# moduloComunicacao2.net
KiCad netlist of a schematic drawn in EAGLE
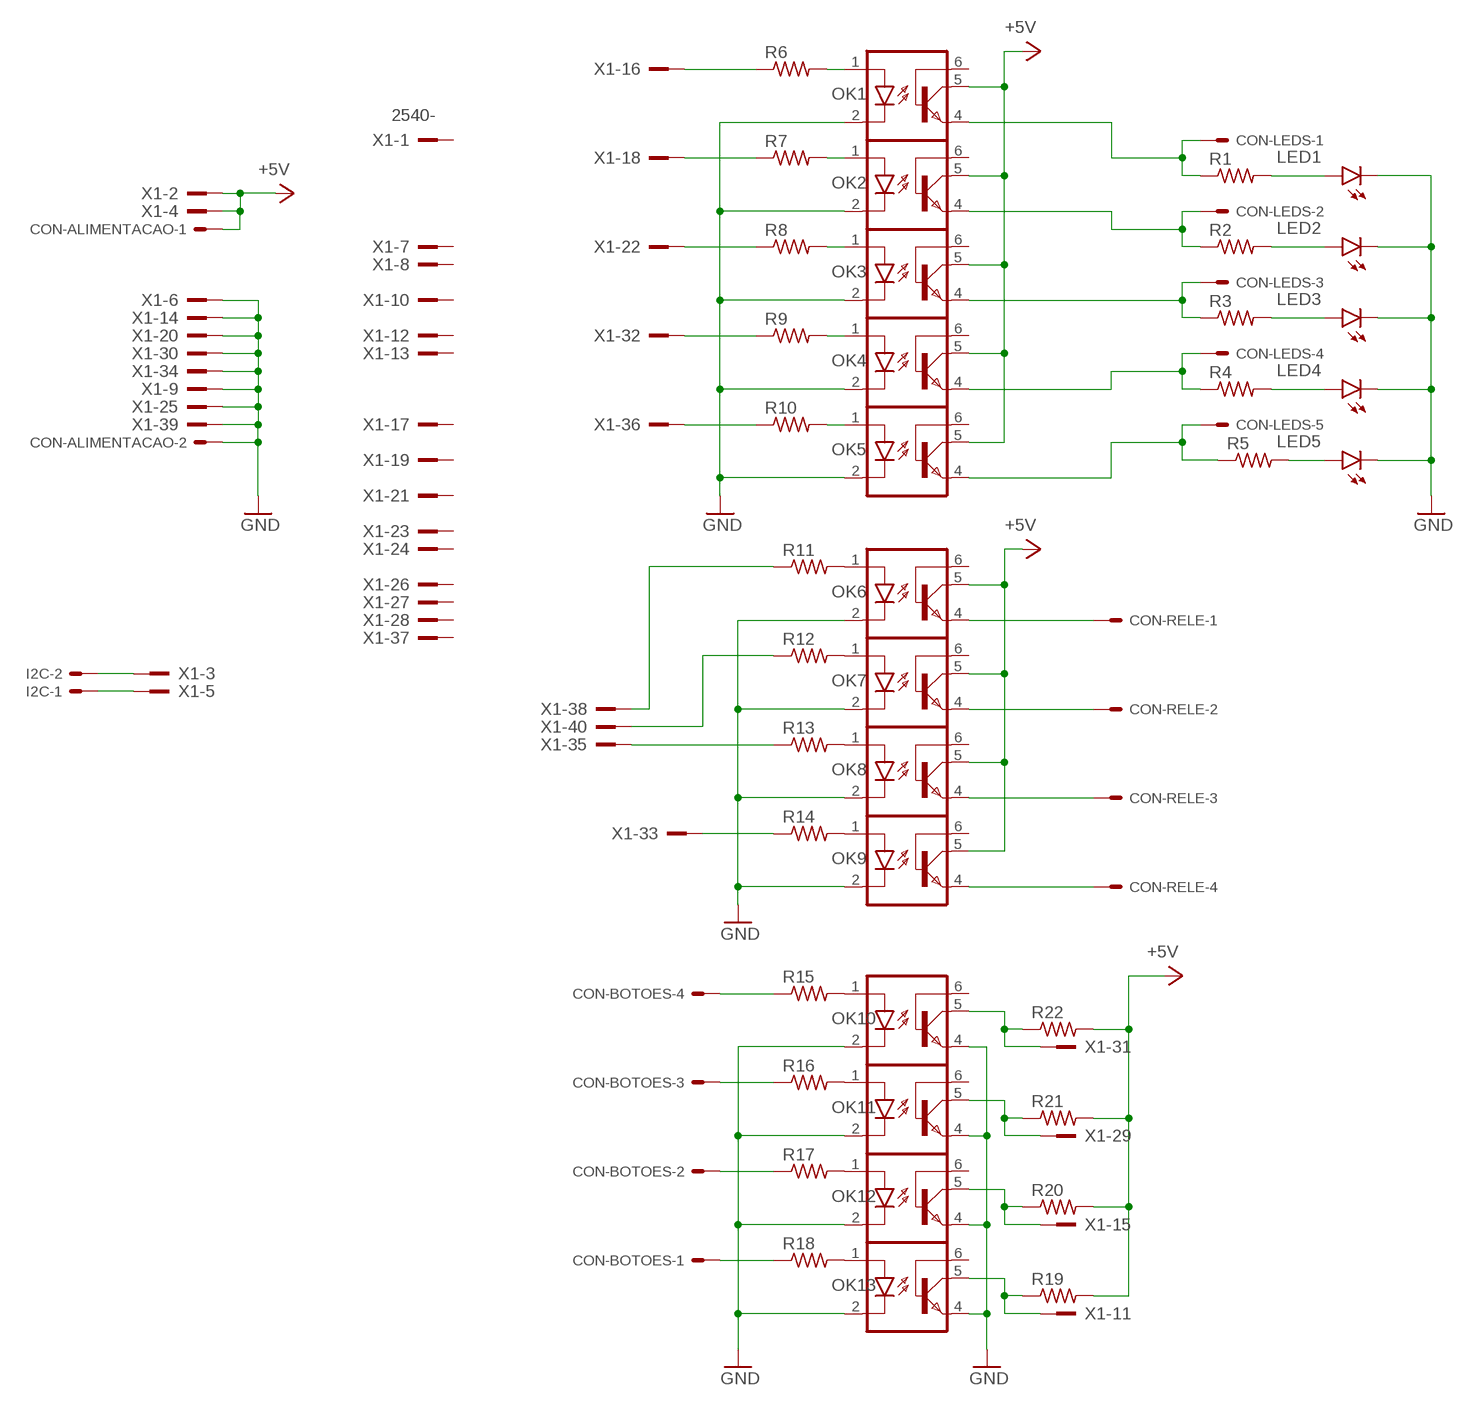
[diagram p0: schematic, sheet 1]

(export (version "E")
  (design (tool "Eeschema 10.0.6"))
  (components
    (comp (ref "CON-ALIMENTACAO")
      (value "22-23-2021")
      (footprint "eagle-import:22-23-2021")
      (fields (field (name "MF") "MOLEX"))
      (libsource (lib "eagle-import") (part "22-23-2021"))
    )
    (comp (ref "CON-BOTOES")
      (value "22-23-2041")
      (footprint "eagle-import:22-23-2041")
      (fields (field (name "MF") "MOLEX"))
      (libsource (lib "eagle-import") (part "22-23-2041"))
    )
    (comp (ref "CON-LEDS")
      (value "22-23-2051")
      (footprint "eagle-import:22-23-2051")
      (fields (field (name "MF") "MOLEX"))
      (libsource (lib "eagle-import") (part "22-23-2051"))
    )
    (comp (ref "CON-RELE")
      (value "22-23-2041")
      (footprint "eagle-import:22-23-2041")
      (fields (field (name "MF") "MOLEX"))
      (libsource (lib "eagle-import") (part "22-23-2041"))
    )
    (comp (ref "I2C")
      (value "22-23-2021")
      (footprint "eagle-import:22-23-2021")
      (fields (field (name "MF") "MOLEX"))
      (libsource (lib "eagle-import") (part "22-23-2021"))
    )
    (comp (ref "LED1")
      (value "LED5MM")
      (footprint "eagle-import:LED5MM")
      (libsource (lib "eagle-import") (part "LED5MM"))
    )
    (comp (ref "LED2")
      (value "LED5MM")
      (footprint "eagle-import:LED5MM")
      (libsource (lib "eagle-import") (part "LED5MM"))
    )
    (comp (ref "LED3")
      (value "LED5MM")
      (footprint "eagle-import:LED5MM")
      (libsource (lib "eagle-import") (part "LED5MM"))
    )
    (comp (ref "LED4")
      (value "LED5MM")
      (footprint "eagle-import:LED5MM")
      (libsource (lib "eagle-import") (part "LED5MM"))
    )
    (comp (ref "LED5")
      (value "LED5MM")
      (footprint "eagle-import:LED5MM")
      (libsource (lib "eagle-import") (part "LED5MM"))
    )
    (comp (ref "OK1")
      (value "4N25M")
      (footprint "eagle-import:DIL06")
      (fields (field (name "MPN") "4N25-M"))
      (libsource (lib "eagle-import") (part "4N?M25"))
    )
    (comp (ref "OK2")
      (value "4N25M")
      (footprint "eagle-import:DIL06")
      (fields (field (name "MPN") "4N25-M"))
      (libsource (lib "eagle-import") (part "4N?M25"))
    )
    (comp (ref "OK3")
      (value "4N25M")
      (footprint "eagle-import:DIL06")
      (fields (field (name "MPN") "4N25-M"))
      (libsource (lib "eagle-import") (part "4N?M25"))
    )
    (comp (ref "OK4")
      (value "4N25M")
      (footprint "eagle-import:DIL06")
      (fields (field (name "MPN") "4N25-M"))
      (libsource (lib "eagle-import") (part "4N?M25"))
    )
    (comp (ref "OK5")
      (value "4N25M")
      (footprint "eagle-import:DIL06")
      (fields (field (name "MPN") "4N25-M"))
      (libsource (lib "eagle-import") (part "4N?M25"))
    )
    (comp (ref "OK6")
      (value "4N25M")
      (footprint "eagle-import:DIL06")
      (fields (field (name "MPN") "4N25-M"))
      (libsource (lib "eagle-import") (part "4N?M25"))
    )
    (comp (ref "OK7")
      (value "4N25M")
      (footprint "eagle-import:DIL06")
      (fields (field (name "MPN") "4N25-M"))
      (libsource (lib "eagle-import") (part "4N?M25"))
    )
    (comp (ref "OK8")
      (value "4N25M")
      (footprint "eagle-import:DIL06")
      (fields (field (name "MPN") "4N25-M"))
      (libsource (lib "eagle-import") (part "4N?M25"))
    )
    (comp (ref "OK9")
      (value "4N25M")
      (footprint "eagle-import:DIL06")
      (fields (field (name "MPN") "4N25-M"))
      (libsource (lib "eagle-import") (part "4N?M25"))
    )
    (comp (ref "OK10")
      (value "4N25M")
      (footprint "eagle-import:DIL06")
      (fields (field (name "MPN") "4N25-M"))
      (libsource (lib "eagle-import") (part "4N?M25"))
    )
    (comp (ref "OK11")
      (value "4N25M")
      (footprint "eagle-import:DIL06")
      (fields (field (name "MPN") "4N25-M"))
      (libsource (lib "eagle-import") (part "4N?M25"))
    )
    (comp (ref "OK12")
      (value "4N25M")
      (footprint "eagle-import:DIL06")
      (fields (field (name "MPN") "4N25-M"))
      (libsource (lib "eagle-import") (part "4N?M25"))
    )
    (comp (ref "OK13")
      (value "4N25M")
      (footprint "eagle-import:DIL06")
      (fields (field (name "MPN") "4N25-M"))
      (libsource (lib "eagle-import") (part "4N?M25"))
    )
    (comp (ref "R1")
      (value "R-US_0207/12")
      (footprint "eagle-import:0207_12")
      (libsource (lib "eagle-import") (part "R-US_0207/12"))
    )
    (comp (ref "R2")
      (value "R-US_0207/12")
      (footprint "eagle-import:0207_12")
      (libsource (lib "eagle-import") (part "R-US_0207/12"))
    )
    (comp (ref "R3")
      (value "R-US_0207/12")
      (footprint "eagle-import:0207_12")
      (libsource (lib "eagle-import") (part "R-US_0207/12"))
    )
    (comp (ref "R4")
      (value "R-US_0207/12")
      (footprint "eagle-import:0207_12")
      (libsource (lib "eagle-import") (part "R-US_0207/12"))
    )
    (comp (ref "R5")
      (value "R-US_0207/12")
      (footprint "eagle-import:0207_12")
      (libsource (lib "eagle-import") (part "R-US_0207/12"))
    )
    (comp (ref "R6")
      (value "R-US_0204/7")
      (footprint "eagle-import:0204_7")
      (libsource (lib "eagle-import") (part "R-US_0204/7"))
    )
    (comp (ref "R7")
      (value "R-US_0204/7")
      (footprint "eagle-import:0204_7")
      (libsource (lib "eagle-import") (part "R-US_0204/7"))
    )
    (comp (ref "R8")
      (value "R-US_0204/7")
      (footprint "eagle-import:0204_7")
      (libsource (lib "eagle-import") (part "R-US_0204/7"))
    )
    (comp (ref "R9")
      (value "R-US_0204/7")
      (footprint "eagle-import:0204_7")
      (libsource (lib "eagle-import") (part "R-US_0204/7"))
    )
    (comp (ref "R10")
      (value "R-US_0204/7")
      (footprint "eagle-import:0204_7")
      (libsource (lib "eagle-import") (part "R-US_0204/7"))
    )
    (comp (ref "R11")
      (value "R-US_0204/7")
      (footprint "eagle-import:0204_7")
      (libsource (lib "eagle-import") (part "R-US_0204/7"))
    )
    (comp (ref "R12")
      (value "R-US_0204/7")
      (footprint "eagle-import:0204_7")
      (libsource (lib "eagle-import") (part "R-US_0204/7"))
    )
    (comp (ref "R13")
      (value "R-US_0204/7")
      (footprint "eagle-import:0204_7")
      (libsource (lib "eagle-import") (part "R-US_0204/7"))
    )
    (comp (ref "R14")
      (value "R-US_0204/7")
      (footprint "eagle-import:0204_7")
      (libsource (lib "eagle-import") (part "R-US_0204/7"))
    )
    (comp (ref "R15")
      (value "R-US_0207/10")
      (footprint "eagle-import:0207_10")
      (libsource (lib "eagle-import") (part "R-US_0207/10"))
    )
    (comp (ref "R16")
      (value "R-US_0207/10")
      (footprint "eagle-import:0207_10")
      (libsource (lib "eagle-import") (part "R-US_0207/10"))
    )
    (comp (ref "R17")
      (value "R-US_0207/10")
      (footprint "eagle-import:0207_10")
      (libsource (lib "eagle-import") (part "R-US_0207/10"))
    )
    (comp (ref "R18")
      (value "R-US_0207/10")
      (footprint "eagle-import:0207_10")
      (libsource (lib "eagle-import") (part "R-US_0207/10"))
    )
    (comp (ref "R19")
      (value "R-US_0204/7")
      (footprint "eagle-import:0204_7")
      (libsource (lib "eagle-import") (part "R-US_0204/7"))
    )
    (comp (ref "R20")
      (value "R-US_0204/7")
      (footprint "eagle-import:0204_7")
      (libsource (lib "eagle-import") (part "R-US_0204/7"))
    )
    (comp (ref "R21")
      (value "R-US_0204/7")
      (footprint "eagle-import:0204_7")
      (libsource (lib "eagle-import") (part "R-US_0204/7"))
    )
    (comp (ref "R22")
      (value "R-US_0204/7")
      (footprint "eagle-import:0204_7")
      (libsource (lib "eagle-import") (part "R-US_0204/7"))
    )
    (comp (ref "X1")
      (value "2540-")
      (footprint "eagle-import:PAK100_2500-40")
      (libsource (lib "eagle-import") (part "2540-"))
    )
  )
  (nets
    (net (code "1") (name "+5V") (class "Default")
      (node (ref "CON-ALIMENTACAO") (pin "1") (pinfunction "S_1") (pintype "passive"))
      (node (ref "OK1") (pin "5") (pinfunction "COL_5") (pintype "passive"))
      (node (ref "OK2") (pin "5") (pinfunction "COL_5") (pintype "passive"))
      (node (ref "OK3") (pin "5") (pinfunction "COL_5") (pintype "passive"))
      (node (ref "OK4") (pin "5") (pinfunction "COL_5") (pintype "passive"))
      (node (ref "OK5") (pin "5") (pinfunction "COL_5") (pintype "passive"))
      (node (ref "OK6") (pin "5") (pinfunction "COL_5") (pintype "passive"))
      (node (ref "OK7") (pin "5") (pinfunction "COL_5") (pintype "passive"))
      (node (ref "OK8") (pin "5") (pinfunction "COL_5") (pintype "passive"))
      (node (ref "OK9") (pin "5") (pinfunction "COL_5") (pintype "passive"))
      (node (ref "R19") (pin "2") (pinfunction "2_2") (pintype "passive"))
      (node (ref "R20") (pin "2") (pinfunction "2_2") (pintype "passive"))
      (node (ref "R21") (pin "2") (pinfunction "2_2") (pintype "passive"))
      (node (ref "R22") (pin "2") (pinfunction "2_2") (pintype "passive"))
      (node (ref "X1") (pin "2") (pinfunction "KL_2") (pintype "passive"))
      (node (ref "X1") (pin "4") (pinfunction "KL_4") (pintype "passive"))
    )
    (net (code "2") (name "GND") (class "Default")
      (node (ref "CON-ALIMENTACAO") (pin "2") (pinfunction "S_2") (pintype "passive"))
      (node (ref "LED1") (pin "K") (pinfunction "C_K") (pintype "passive"))
      (node (ref "LED2") (pin "K") (pinfunction "C_K") (pintype "passive"))
      (node (ref "LED3") (pin "K") (pinfunction "C_K") (pintype "passive"))
      (node (ref "LED4") (pin "K") (pinfunction "C_K") (pintype "passive"))
      (node (ref "LED5") (pin "K") (pinfunction "C_K") (pintype "passive"))
      (node (ref "OK1") (pin "2") (pinfunction "C_2") (pintype "passive"))
      (node (ref "OK10") (pin "2") (pinfunction "C_2") (pintype "passive"))
      (node (ref "OK10") (pin "4") (pinfunction "EMI_4") (pintype "passive"))
      (node (ref "OK11") (pin "2") (pinfunction "C_2") (pintype "passive"))
      (node (ref "OK11") (pin "4") (pinfunction "EMI_4") (pintype "passive"))
      (node (ref "OK12") (pin "2") (pinfunction "C_2") (pintype "passive"))
      (node (ref "OK12") (pin "4") (pinfunction "EMI_4") (pintype "passive"))
      (node (ref "OK13") (pin "2") (pinfunction "C_2") (pintype "passive"))
      (node (ref "OK13") (pin "4") (pinfunction "EMI_4") (pintype "passive"))
      (node (ref "OK2") (pin "2") (pinfunction "C_2") (pintype "passive"))
      (node (ref "OK3") (pin "2") (pinfunction "C_2") (pintype "passive"))
      (node (ref "OK4") (pin "2") (pinfunction "C_2") (pintype "passive"))
      (node (ref "OK5") (pin "2") (pinfunction "C_2") (pintype "passive"))
      (node (ref "OK6") (pin "2") (pinfunction "C_2") (pintype "passive"))
      (node (ref "OK7") (pin "2") (pinfunction "C_2") (pintype "passive"))
      (node (ref "OK8") (pin "2") (pinfunction "C_2") (pintype "passive"))
      (node (ref "OK9") (pin "2") (pinfunction "C_2") (pintype "passive"))
      (node (ref "X1") (pin "14") (pinfunction "KL_14") (pintype "passive"))
      (node (ref "X1") (pin "20") (pinfunction "KL_20") (pintype "passive"))
      (node (ref "X1") (pin "25") (pinfunction "KL_25") (pintype "passive"))
      (node (ref "X1") (pin "30") (pinfunction "KL_30") (pintype "passive"))
      (node (ref "X1") (pin "34") (pinfunction "KL_34") (pintype "passive"))
      (node (ref "X1") (pin "39") (pinfunction "KL_39") (pintype "passive"))
      (node (ref "X1") (pin "6") (pinfunction "KL_6") (pintype "passive"))
      (node (ref "X1") (pin "9") (pinfunction "KL_9") (pintype "passive"))
    )
    (net (code "3") (name "Net-(CON-BOTOESA-S)") (class "Default")
      (node (ref "CON-BOTOES") (pin "1") (pinfunction "S_1") (pintype "passive"))
      (node (ref "R18") (pin "1") (pinfunction "1_1") (pintype "passive"))
    )
    (net (code "4") (name "Net-(CON-BOTOESB-S)") (class "Default")
      (node (ref "CON-BOTOES") (pin "2") (pinfunction "S_2") (pintype "passive"))
      (node (ref "R17") (pin "1") (pinfunction "1_1") (pintype "passive"))
    )
    (net (code "5") (name "Net-(CON-BOTOESC-S)") (class "Default")
      (node (ref "CON-BOTOES") (pin "3") (pinfunction "S_3") (pintype "passive"))
      (node (ref "R16") (pin "1") (pinfunction "1_1") (pintype "passive"))
    )
    (net (code "6") (name "Net-(CON-BOTOESD-S)") (class "Default")
      (node (ref "CON-BOTOES") (pin "4") (pinfunction "S_4") (pintype "passive"))
      (node (ref "R15") (pin "1") (pinfunction "1_1") (pintype "passive"))
    )
    (net (code "7") (name "Net-(CON-LEDSA-S)") (class "Default")
      (node (ref "CON-LEDS") (pin "1") (pinfunction "S_1") (pintype "passive"))
      (node (ref "OK1") (pin "4") (pinfunction "EMI_4") (pintype "passive"))
      (node (ref "R1") (pin "1") (pinfunction "1_1") (pintype "passive"))
    )
    (net (code "8") (name "Net-(CON-LEDSB-S)") (class "Default")
      (node (ref "CON-LEDS") (pin "2") (pinfunction "S_2") (pintype "passive"))
      (node (ref "OK2") (pin "4") (pinfunction "EMI_4") (pintype "passive"))
      (node (ref "R2") (pin "1") (pinfunction "1_1") (pintype "passive"))
    )
    (net (code "9") (name "Net-(CON-LEDSC-S)") (class "Default")
      (node (ref "CON-LEDS") (pin "3") (pinfunction "S_3") (pintype "passive"))
      (node (ref "OK3") (pin "4") (pinfunction "EMI_4") (pintype "passive"))
      (node (ref "R3") (pin "1") (pinfunction "1_1") (pintype "passive"))
    )
    (net (code "10") (name "Net-(CON-LEDSD-S)") (class "Default")
      (node (ref "CON-LEDS") (pin "4") (pinfunction "S_4") (pintype "passive"))
      (node (ref "OK4") (pin "4") (pinfunction "EMI_4") (pintype "passive"))
      (node (ref "R4") (pin "1") (pinfunction "1_1") (pintype "passive"))
    )
    (net (code "11") (name "Net-(CON-LEDSE-S)") (class "Default")
      (node (ref "CON-LEDS") (pin "5") (pinfunction "S_5") (pintype "passive"))
      (node (ref "OK5") (pin "4") (pinfunction "EMI_4") (pintype "passive"))
      (node (ref "R5") (pin "1") (pinfunction "1_1") (pintype "passive"))
    )
    (net (code "12") (name "Net-(CON-RELEA-S)") (class "Default")
      (node (ref "CON-RELE") (pin "1") (pinfunction "S_1") (pintype "passive"))
      (node (ref "OK6") (pin "4") (pinfunction "EMI_4") (pintype "passive"))
    )
    (net (code "13") (name "Net-(CON-RELEB-S)") (class "Default")
      (node (ref "CON-RELE") (pin "2") (pinfunction "S_2") (pintype "passive"))
      (node (ref "OK7") (pin "4") (pinfunction "EMI_4") (pintype "passive"))
    )
    (net (code "14") (name "Net-(CON-RELEC-S)") (class "Default")
      (node (ref "CON-RELE") (pin "3") (pinfunction "S_3") (pintype "passive"))
      (node (ref "OK8") (pin "4") (pinfunction "EMI_4") (pintype "passive"))
    )
    (net (code "15") (name "Net-(CON-RELED-S)") (class "Default")
      (node (ref "CON-RELE") (pin "4") (pinfunction "S_4") (pintype "passive"))
      (node (ref "OK9") (pin "4") (pinfunction "EMI_4") (pintype "passive"))
    )
    (net (code "16") (name "Net-(I2CA-S)") (class "Default")
      (node (ref "I2C") (pin "1") (pinfunction "S_1") (pintype "passive"))
      (node (ref "X1") (pin "5") (pinfunction "KL_5") (pintype "passive"))
    )
    (net (code "17") (name "Net-(I2CB-S)") (class "Default")
      (node (ref "I2C") (pin "2") (pinfunction "S_2") (pintype "passive"))
      (node (ref "X1") (pin "3") (pinfunction "KL_3") (pintype "passive"))
    )
    (net (code "18") (name "Net-(LED1-PadA)") (class "Default")
      (node (ref "LED1") (pin "A") (pinfunction "A_A") (pintype "passive"))
      (node (ref "R1") (pin "2") (pinfunction "2_2") (pintype "passive"))
    )
    (net (code "19") (name "Net-(LED2-PadA)") (class "Default")
      (node (ref "LED2") (pin "A") (pinfunction "A_A") (pintype "passive"))
      (node (ref "R2") (pin "2") (pinfunction "2_2") (pintype "passive"))
    )
    (net (code "20") (name "Net-(LED3-PadA)") (class "Default")
      (node (ref "LED3") (pin "A") (pinfunction "A_A") (pintype "passive"))
      (node (ref "R3") (pin "2") (pinfunction "2_2") (pintype "passive"))
    )
    (net (code "21") (name "Net-(LED4-PadA)") (class "Default")
      (node (ref "LED4") (pin "A") (pinfunction "A_A") (pintype "passive"))
      (node (ref "R4") (pin "2") (pinfunction "2_2") (pintype "passive"))
    )
    (net (code "22") (name "Net-(LED5-PadA)") (class "Default")
      (node (ref "LED5") (pin "A") (pinfunction "A_A") (pintype "passive"))
      (node (ref "R5") (pin "2") (pinfunction "2_2") (pintype "passive"))
    )
    (net (code "23") (name "Net-(OK1-A)") (class "Default")
      (node (ref "OK1") (pin "1") (pinfunction "A_1") (pintype "passive"))
      (node (ref "R6") (pin "2") (pinfunction "2_2") (pintype "passive"))
    )
    (net (code "24") (name "Net-(OK2-A)") (class "Default")
      (node (ref "OK2") (pin "1") (pinfunction "A_1") (pintype "passive"))
      (node (ref "R7") (pin "2") (pinfunction "2_2") (pintype "passive"))
    )
    (net (code "25") (name "Net-(OK3-A)") (class "Default")
      (node (ref "OK3") (pin "1") (pinfunction "A_1") (pintype "passive"))
      (node (ref "R8") (pin "2") (pinfunction "2_2") (pintype "passive"))
    )
    (net (code "26") (name "Net-(OK4-A)") (class "Default")
      (node (ref "OK4") (pin "1") (pinfunction "A_1") (pintype "passive"))
      (node (ref "R9") (pin "2") (pinfunction "2_2") (pintype "passive"))
    )
    (net (code "27") (name "Net-(OK5-A)") (class "Default")
      (node (ref "OK5") (pin "1") (pinfunction "A_1") (pintype "passive"))
      (node (ref "R10") (pin "2") (pinfunction "2_2") (pintype "passive"))
    )
    (net (code "28") (name "Net-(OK6-A)") (class "Default")
      (node (ref "OK6") (pin "1") (pinfunction "A_1") (pintype "passive"))
      (node (ref "R11") (pin "2") (pinfunction "2_2") (pintype "passive"))
    )
    (net (code "29") (name "Net-(OK7-A)") (class "Default")
      (node (ref "OK7") (pin "1") (pinfunction "A_1") (pintype "passive"))
      (node (ref "R12") (pin "2") (pinfunction "2_2") (pintype "passive"))
    )
    (net (code "30") (name "Net-(OK8-A)") (class "Default")
      (node (ref "OK8") (pin "1") (pinfunction "A_1") (pintype "passive"))
      (node (ref "R13") (pin "2") (pinfunction "2_2") (pintype "passive"))
    )
    (net (code "31") (name "Net-(OK9-A)") (class "Default")
      (node (ref "OK9") (pin "1") (pinfunction "A_1") (pintype "passive"))
      (node (ref "R14") (pin "2") (pinfunction "2_2") (pintype "passive"))
    )
    (net (code "32") (name "Net-(OK10-A)") (class "Default")
      (node (ref "OK10") (pin "1") (pinfunction "A_1") (pintype "passive"))
      (node (ref "R15") (pin "2") (pinfunction "2_2") (pintype "passive"))
    )
    (net (code "33") (name "Net-(OK10-COL)") (class "Default")
      (node (ref "OK10") (pin "5") (pinfunction "COL_5") (pintype "passive"))
      (node (ref "R22") (pin "1") (pinfunction "1_1") (pintype "passive"))
      (node (ref "X1") (pin "31") (pinfunction "KL_31") (pintype "passive"))
    )
    (net (code "34") (name "Net-(OK11-A)") (class "Default")
      (node (ref "OK11") (pin "1") (pinfunction "A_1") (pintype "passive"))
      (node (ref "R16") (pin "2") (pinfunction "2_2") (pintype "passive"))
    )
    (net (code "35") (name "Net-(OK11-COL)") (class "Default")
      (node (ref "OK11") (pin "5") (pinfunction "COL_5") (pintype "passive"))
      (node (ref "R21") (pin "1") (pinfunction "1_1") (pintype "passive"))
      (node (ref "X1") (pin "29") (pinfunction "KL_29") (pintype "passive"))
    )
    (net (code "36") (name "Net-(OK12-A)") (class "Default")
      (node (ref "OK12") (pin "1") (pinfunction "A_1") (pintype "passive"))
      (node (ref "R17") (pin "2") (pinfunction "2_2") (pintype "passive"))
    )
    (net (code "37") (name "Net-(OK12-COL)") (class "Default")
      (node (ref "OK12") (pin "5") (pinfunction "COL_5") (pintype "passive"))
      (node (ref "R20") (pin "1") (pinfunction "1_1") (pintype "passive"))
      (node (ref "X1") (pin "15") (pinfunction "KL_15") (pintype "passive"))
    )
    (net (code "38") (name "Net-(OK13-A)") (class "Default")
      (node (ref "OK13") (pin "1") (pinfunction "A_1") (pintype "passive"))
      (node (ref "R18") (pin "2") (pinfunction "2_2") (pintype "passive"))
    )
    (net (code "39") (name "Net-(OK13-COL)") (class "Default")
      (node (ref "OK13") (pin "5") (pinfunction "COL_5") (pintype "passive"))
      (node (ref "R19") (pin "1") (pinfunction "1_1") (pintype "passive"))
      (node (ref "X1") (pin "11") (pinfunction "KL_11") (pintype "passive"))
    )
    (net (code "40") (name "Net-(X1AA-KL)") (class "Default")
      (node (ref "R14") (pin "1") (pinfunction "1_1") (pintype "passive"))
      (node (ref "X1") (pin "33") (pinfunction "KL_33") (pintype "passive"))
    )
    (net (code "41") (name "Net-(X1AC-KL)") (class "Default")
      (node (ref "R13") (pin "1") (pinfunction "1_1") (pintype "passive"))
      (node (ref "X1") (pin "35") (pinfunction "KL_35") (pintype "passive"))
    )
    (net (code "42") (name "Net-(X1AD-KL)") (class "Default")
      (node (ref "R10") (pin "1") (pinfunction "1_1") (pintype "passive"))
      (node (ref "X1") (pin "36") (pinfunction "KL_36") (pintype "passive"))
    )
    (net (code "43") (name "Net-(X1AF-KL)") (class "Default")
      (node (ref "R11") (pin "1") (pinfunction "1_1") (pintype "passive"))
      (node (ref "X1") (pin "38") (pinfunction "KL_38") (pintype "passive"))
    )
    (net (code "44") (name "Net-(X1AI-KL)") (class "Default")
      (node (ref "R12") (pin "1") (pinfunction "1_1") (pintype "passive"))
      (node (ref "X1") (pin "40") (pinfunction "KL_40") (pintype "passive"))
    )
    (net (code "45") (name "Net-(X1H-KL)") (class "Default")
      (node (ref "R6") (pin "1") (pinfunction "1_1") (pintype "passive"))
      (node (ref "X1") (pin "16") (pinfunction "KL_16") (pintype "passive"))
    )
    (net (code "46") (name "Net-(X1J-KL)") (class "Default")
      (node (ref "R7") (pin "1") (pinfunction "1_1") (pintype "passive"))
      (node (ref "X1") (pin "18") (pinfunction "KL_18") (pintype "passive"))
    )
    (net (code "47") (name "Net-(X1O-KL)") (class "Default")
      (node (ref "R8") (pin "1") (pinfunction "1_1") (pintype "passive"))
      (node (ref "X1") (pin "22") (pinfunction "KL_22") (pintype "passive"))
    )
    (net (code "48") (name "Net-(X1Z-KL)") (class "Default")
      (node (ref "R9") (pin "1") (pinfunction "1_1") (pintype "passive"))
      (node (ref "X1") (pin "32") (pinfunction "KL_32") (pintype "passive"))
    )
    (net (code "49") (name "unconnected-(OK1-BAS-Pad6)") (class "Default")
      (node (ref "OK1") (pin "6") (pinfunction "BAS_6") (pintype "passive"))
    )
    (net (code "50") (name "unconnected-(OK2-BAS-Pad6)") (class "Default")
      (node (ref "OK2") (pin "6") (pinfunction "BAS_6") (pintype "passive"))
    )
    (net (code "51") (name "unconnected-(OK3-BAS-Pad6)") (class "Default")
      (node (ref "OK3") (pin "6") (pinfunction "BAS_6") (pintype "passive"))
    )
    (net (code "52") (name "unconnected-(OK4-BAS-Pad6)") (class "Default")
      (node (ref "OK4") (pin "6") (pinfunction "BAS_6") (pintype "passive"))
    )
    (net (code "53") (name "unconnected-(OK5-BAS-Pad6)") (class "Default")
      (node (ref "OK5") (pin "6") (pinfunction "BAS_6") (pintype "passive"))
    )
    (net (code "54") (name "unconnected-(OK6-BAS-Pad6)") (class "Default")
      (node (ref "OK6") (pin "6") (pinfunction "BAS_6") (pintype "passive"))
    )
    (net (code "55") (name "unconnected-(OK7-BAS-Pad6)") (class "Default")
      (node (ref "OK7") (pin "6") (pinfunction "BAS_6") (pintype "passive"))
    )
    (net (code "56") (name "unconnected-(OK8-BAS-Pad6)") (class "Default")
      (node (ref "OK8") (pin "6") (pinfunction "BAS_6") (pintype "passive"))
    )
    (net (code "57") (name "unconnected-(OK9-BAS-Pad6)") (class "Default")
      (node (ref "OK9") (pin "6") (pinfunction "BAS_6") (pintype "passive"))
    )
    (net (code "58") (name "unconnected-(OK10-BAS-Pad6)") (class "Default")
      (node (ref "OK10") (pin "6") (pinfunction "BAS_6") (pintype "passive"))
    )
    (net (code "59") (name "unconnected-(OK11-BAS-Pad6)") (class "Default")
      (node (ref "OK11") (pin "6") (pinfunction "BAS_6") (pintype "passive"))
    )
    (net (code "60") (name "unconnected-(OK12-BAS-Pad6)") (class "Default")
      (node (ref "OK12") (pin "6") (pinfunction "BAS_6") (pintype "passive"))
    )
    (net (code "61") (name "unconnected-(OK13-BAS-Pad6)") (class "Default")
      (node (ref "OK13") (pin "6") (pinfunction "BAS_6") (pintype "passive"))
    )
    (net (code "62") (name "unconnected-(X1A-KL-Pad1)") (class "Default")
      (node (ref "X1") (pin "1") (pinfunction "KL_1") (pintype "passive"))
    )
    (net (code "63") (name "unconnected-(X1AE-KL-Pad37)") (class "Default")
      (node (ref "X1") (pin "37") (pinfunction "KL_37") (pintype "passive"))
    )
    (net (code "64") (name "unconnected-(X1AL-KL-Pad7)") (class "Default")
      (node (ref "X1") (pin "7") (pinfunction "KL_7") (pintype "passive"))
    )
    (net (code "65") (name "unconnected-(X1AM-KL-Pad8)") (class "Default")
      (node (ref "X1") (pin "8") (pinfunction "KL_8") (pintype "passive"))
    )
    (net (code "66") (name "unconnected-(X1B-KL-Pad10)") (class "Default")
      (node (ref "X1") (pin "10") (pinfunction "KL_10") (pintype "passive"))
    )
    (net (code "67") (name "unconnected-(X1D-KL-Pad12)") (class "Default")
      (node (ref "X1") (pin "12") (pinfunction "KL_12") (pintype "passive"))
    )
    (net (code "68") (name "unconnected-(X1E-KL-Pad13)") (class "Default")
      (node (ref "X1") (pin "13") (pinfunction "KL_13") (pintype "passive"))
    )
    (net (code "69") (name "unconnected-(X1I-KL-Pad17)") (class "Default")
      (node (ref "X1") (pin "17") (pinfunction "KL_17") (pintype "passive"))
    )
    (net (code "70") (name "unconnected-(X1K-KL-Pad19)") (class "Default")
      (node (ref "X1") (pin "19") (pinfunction "KL_19") (pintype "passive"))
    )
    (net (code "71") (name "unconnected-(X1N-KL-Pad21)") (class "Default")
      (node (ref "X1") (pin "21") (pinfunction "KL_21") (pintype "passive"))
    )
    (net (code "72") (name "unconnected-(X1P-KL-Pad23)") (class "Default")
      (node (ref "X1") (pin "23") (pinfunction "KL_23") (pintype "passive"))
    )
    (net (code "73") (name "unconnected-(X1Q-KL-Pad24)") (class "Default")
      (node (ref "X1") (pin "24") (pinfunction "KL_24") (pintype "passive"))
    )
    (net (code "74") (name "unconnected-(X1S-KL-Pad26)") (class "Default")
      (node (ref "X1") (pin "26") (pinfunction "KL_26") (pintype "passive"))
    )
    (net (code "75") (name "unconnected-(X1T-KL-Pad27)") (class "Default")
      (node (ref "X1") (pin "27") (pinfunction "KL_27") (pintype "passive"))
    )
    (net (code "76") (name "unconnected-(X1U-KL-Pad28)") (class "Default")
      (node (ref "X1") (pin "28") (pinfunction "KL_28") (pintype "passive"))
    )
  )
)
